# re-bent_hum_singe.net
KiCad netlist of a schematic drawn in EAGLE
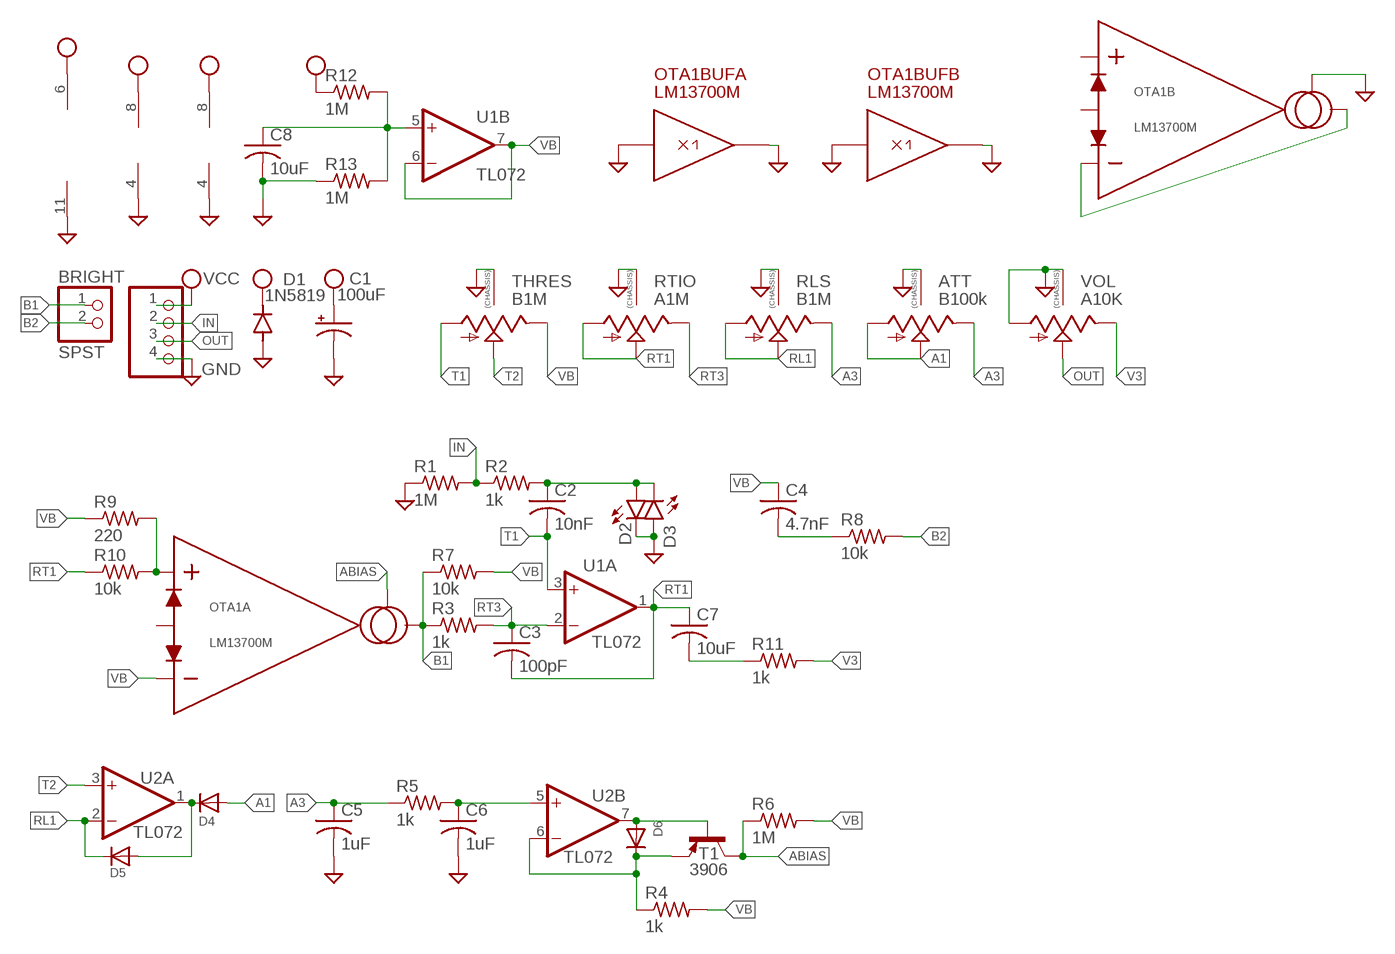
[diagram p0: schematic, sheet 1]

(export (version "E")
  (design (tool "Eeschema 10.0.6"))
  (components
    (comp (ref "ATT")
      (value "B100k")
      (footprint "eagle-import:9MM_SNAP-IN_POT")
      (libsource (lib "eagle-import") (part "9MM_SNAP-IN_POT_CHASSIS"))
    )
    (comp (ref "BRIGHT")
      (value "SPST")
      (footprint "eagle-import:1X02")
      (libsource (lib "eagle-import") (part "PINHD-1X2"))
    )
    (comp (ref "C1")
      (value "100uF")
      (footprint "eagle-import:PAN_B_SMD+THRU")
      (libsource (lib "eagle-import") (part "CAP_SMD+THRUPAN_B"))
    )
    (comp (ref "C2")
      (value "10nF")
      (footprint "eagle-import:C0603")
      (libsource (lib "eagle-import") (part "adafruit_420_C-USC0603"))
    )
    (comp (ref "C3")
      (value "100pF")
      (footprint "eagle-import:C0603")
      (libsource (lib "eagle-import") (part "adafruit_420_C-USC0603"))
    )
    (comp (ref "C4")
      (value "4.7nF")
      (footprint "eagle-import:C0603")
      (libsource (lib "eagle-import") (part "adafruit_420_C-USC0603"))
    )
    (comp (ref "C5")
      (value "1uF")
      (footprint "eagle-import:C0805")
      (libsource (lib "eagle-import") (part "C-USC0805"))
    )
    (comp (ref "C6")
      (value "1uF")
      (footprint "eagle-import:C0805")
      (libsource (lib "eagle-import") (part "C-USC0805"))
    )
    (comp (ref "C7")
      (value "10uF")
      (footprint "eagle-import:C1206")
      (libsource (lib "eagle-import") (part "C-USC1206"))
    )
    (comp (ref "C8")
      (value "10uF")
      (footprint "eagle-import:C1206")
      (libsource (lib "eagle-import") (part "C-USC1206"))
    )
    (comp (ref "D1")
      (value "1N5819")
      (footprint "eagle-import:SOD123")
      (libsource (lib "eagle-import") (part "DIODE-SOD123"))
    )
    (comp (ref "D2")
      (value "LED0603")
      (footprint "eagle-import:LED-0603")
      (libsource (lib "eagle-import") (part "LED0603"))
    )
    (comp (ref "D3")
      (value "LED0603")
      (footprint "eagle-import:LED-0603")
      (libsource (lib "eagle-import") (part "LED0603"))
    )
    (comp (ref "D4")
      (value "DIODESOD-123")
      (footprint "eagle-import:SOD-123")
      (libsource (lib "eagle-import") (part "DIODESOD-123"))
    )
    (comp (ref "D5")
      (value "DIODESOD-123")
      (footprint "eagle-import:SOD-123")
      (libsource (lib "eagle-import") (part "DIODESOD-123"))
    )
    (comp (ref "D6")
      (value "DIODESOD-123")
      (footprint "eagle-import:SOD-123")
      (libsource (lib "eagle-import") (part "DIODESOD-123"))
    )
    (comp (ref "JP1")
      (value "PINHD-1X4")
      (footprint "eagle-import:1X04")
      (libsource (lib "eagle-import") (part "PINHD-1X4"))
    )
    (comp (ref "OTA1")
      (value "LM13700M")
      (footprint "eagle-import:SO16")
      (libsource (lib "eagle-import") (part "LM13700M"))
    )
    (comp (ref "R1")
      (value "1M")
      (footprint "eagle-import:R0603")
      (libsource (lib "eagle-import") (part "R-US_R0603"))
    )
    (comp (ref "R2")
      (value "1k")
      (footprint "eagle-import:R0603")
      (libsource (lib "eagle-import") (part "R-US_R0603"))
    )
    (comp (ref "R3")
      (value "1k")
      (footprint "eagle-import:R0603")
      (libsource (lib "eagle-import") (part "R-US_R0603"))
    )
    (comp (ref "R4")
      (value "1k")
      (footprint "eagle-import:R0603")
      (libsource (lib "eagle-import") (part "R-US_R0603"))
    )
    (comp (ref "R5")
      (value "1k")
      (footprint "eagle-import:R0603")
      (libsource (lib "eagle-import") (part "R-US_R0603"))
    )
    (comp (ref "R6")
      (value "1M")
      (footprint "eagle-import:R0603")
      (libsource (lib "eagle-import") (part "R-US_R0603"))
    )
    (comp (ref "R7")
      (value "10k")
      (footprint "eagle-import:R0603")
      (libsource (lib "eagle-import") (part "R-US_R0603"))
    )
    (comp (ref "R8")
      (value "10k")
      (footprint "eagle-import:R0603")
      (libsource (lib "eagle-import") (part "R-US_R0603"))
    )
    (comp (ref "R9")
      (value "220")
      (footprint "eagle-import:R0603")
      (libsource (lib "eagle-import") (part "R-US_R0603"))
    )
    (comp (ref "R10")
      (value "10k")
      (footprint "eagle-import:R0603")
      (libsource (lib "eagle-import") (part "R-US_R0603"))
    )
    (comp (ref "R11")
      (value "1k")
      (footprint "eagle-import:R0603")
      (libsource (lib "eagle-import") (part "R-US_R0603"))
    )
    (comp (ref "R12")
      (value "1M")
      (footprint "eagle-import:R0603")
      (libsource (lib "eagle-import") (part "R-US_R0603"))
    )
    (comp (ref "R13")
      (value "1M")
      (footprint "eagle-import:R0603")
      (libsource (lib "eagle-import") (part "R-US_R0603"))
    )
    (comp (ref "RLS")
      (value "B1M")
      (footprint "eagle-import:9MM_SNAP-IN_POT")
      (libsource (lib "eagle-import") (part "9MM_SNAP-IN_POT_CHASSIS"))
    )
    (comp (ref "RTIO")
      (value "A1M")
      (footprint "eagle-import:9MM_SNAP-IN_POT")
      (libsource (lib "eagle-import") (part "9MM_SNAP-IN_POT_CHASSIS"))
    )
    (comp (ref "T1")
      (value "3906")
      (footprint "eagle-import:SOT23-BEC")
      (libsource (lib "eagle-import") (part "-PNP-SOT23-BECMMBT3906LT1"))
    )
    (comp (ref "THRES")
      (value "B1M")
      (footprint "eagle-import:9MM_SNAP-IN_POT")
      (libsource (lib "eagle-import") (part "9MM_SNAP-IN_POT_CHASSIS"))
    )
    (comp (ref "U1")
      (value "TL072")
      (footprint "eagle-import:TSSOP-8")
      (libsource (lib "eagle-import") (part "TL072TSSOP"))
    )
    (comp (ref "U2")
      (value "TL072")
      (footprint "eagle-import:TSSOP-8")
      (libsource (lib "eagle-import") (part "TL072TSSOP"))
    )
    (comp (ref "VOL")
      (value "A10K")
      (footprint "eagle-import:9MM_SNAP-IN_POT")
      (libsource (lib "eagle-import") (part "9MM_SNAP-IN_POT_CHASSIS"))
    )
  )
  (nets
    (net (code "1") (name "A1") (class "Default")
      (node (ref "ATT") (pin "1") (pinfunction "A_1") (pintype "passive"))
      (node (ref "ATT") (pin "2") (pinfunction "S_2") (pintype "passive"))
      (node (ref "D4") (pin "A") (pinfunction "A_A") (pintype "passive"))
    )
    (net (code "2") (name "A3") (class "Default")
      (node (ref "ATT") (pin "3") (pinfunction "E_3") (pintype "passive"))
      (node (ref "C5") (pin "1") (pinfunction "1_1") (pintype "passive"))
      (node (ref "R5") (pin "1") (pinfunction "1_1") (pintype "passive"))
      (node (ref "RLS") (pin "3") (pinfunction "E_3") (pintype "passive"))
    )
    (net (code "3") (name "ABIAS") (class "Default")
      (node (ref "OTA1") (pin "1") (pinfunction "IABC_1") (pintype "input"))
      (node (ref "R6") (pin "1") (pinfunction "1_1") (pintype "passive"))
      (node (ref "T1") (pin "C") (pinfunction "C_C") (pintype "passive"))
    )
    (net (code "4") (name "B1") (class "Default")
      (node (ref "BRIGHT") (pin "1") (pinfunction "1_1") (pintype "passive"))
      (node (ref "OTA1") (pin "5") (pinfunction "IOUT_5") (pintype "output"))
      (node (ref "R3") (pin "1") (pinfunction "1_1") (pintype "passive"))
      (node (ref "R7") (pin "1") (pinfunction "1_1") (pintype "passive"))
    )
    (net (code "5") (name "B2") (class "Default")
      (node (ref "BRIGHT") (pin "2") (pinfunction "2_2") (pintype "passive"))
      (node (ref "R8") (pin "2") (pinfunction "2_2") (pintype "passive"))
    )
    (net (code "6") (name "GND") (class "Default")
      (node (ref "ATT") (pin "CHASSIS1") (pinfunction "P$1_CHASSIS1") (pintype "passive"))
      (node (ref "ATT") (pin "CHASSIS2") (pinfunction "P$1_CHASSIS2") (pintype "passive"))
      (node (ref "C1") (pin "-") (pinfunction "-_-") (pintype "passive"))
      (node (ref "C1") (pin "--") (pinfunction "-_--") (pintype "passive"))
      (node (ref "C5") (pin "2") (pinfunction "2_2") (pintype "passive"))
      (node (ref "C6") (pin "2") (pinfunction "2_2") (pintype "passive"))
      (node (ref "C8") (pin "2") (pinfunction "2_2") (pintype "passive"))
      (node (ref "D1") (pin "A") (pinfunction "A_A") (pintype "passive"))
      (node (ref "D2") (pin "C") (pinfunction "C_C") (pintype "passive"))
      (node (ref "D3") (pin "A") (pinfunction "A_A") (pintype "passive"))
      (node (ref "JP1") (pin "4") (pinfunction "4_4") (pintype "passive"))
      (node (ref "OTA1") (pin "11") (pinfunction "VEE_11") (pintype "power_in"))
      (node (ref "OTA1") (pin "16") (pinfunction "IABC_16") (pintype "input"))
      (node (ref "OTA1") (pin "8") (pinfunction "OUT_8") (pintype "bidirectional"))
      (node (ref "OTA1") (pin "9") (pinfunction "OUT_9") (pintype "bidirectional"))
      (node (ref "R1") (pin "1") (pinfunction "1_1") (pintype "passive"))
      (node (ref "R13") (pin "1") (pinfunction "1_1") (pintype "passive"))
      (node (ref "RLS") (pin "CHASSIS1") (pinfunction "P$1_CHASSIS1") (pintype "passive"))
      (node (ref "RLS") (pin "CHASSIS2") (pinfunction "P$1_CHASSIS2") (pintype "passive"))
      (node (ref "RTIO") (pin "CHASSIS1") (pinfunction "P$1_CHASSIS1") (pintype "passive"))
      (node (ref "RTIO") (pin "CHASSIS2") (pinfunction "P$1_CHASSIS2") (pintype "passive"))
      (node (ref "THRES") (pin "CHASSIS1") (pinfunction "P$1_CHASSIS1") (pintype "passive"))
      (node (ref "THRES") (pin "CHASSIS2") (pinfunction "P$1_CHASSIS2") (pintype "passive"))
      (node (ref "U1") (pin "4") (pinfunction "V-_4") (pintype "power_in"))
      (node (ref "U2") (pin "4") (pinfunction "V-_4") (pintype "power_in"))
      (node (ref "VOL") (pin "1") (pinfunction "A_1") (pintype "passive"))
      (node (ref "VOL") (pin "CHASSIS1") (pinfunction "P$1_CHASSIS1") (pintype "passive"))
      (node (ref "VOL") (pin "CHASSIS2") (pinfunction "P$1_CHASSIS2") (pintype "passive"))
    )
    (net (code "7") (name "IN") (class "Default")
      (node (ref "JP1") (pin "2") (pinfunction "2_2") (pintype "passive"))
      (node (ref "R1") (pin "2") (pinfunction "2_2") (pintype "passive"))
      (node (ref "R2") (pin "1") (pinfunction "1_1") (pintype "passive"))
    )
    (net (code "8") (name "Net-(C2-Pad1)") (class "Default")
      (node (ref "C2") (pin "1") (pinfunction "1_1") (pintype "passive"))
      (node (ref "D2") (pin "A") (pinfunction "A_A") (pintype "passive"))
      (node (ref "D3") (pin "C") (pinfunction "C_C") (pintype "passive"))
      (node (ref "R2") (pin "2") (pinfunction "2_2") (pintype "passive"))
    )
    (net (code "9") (name "Net-(C4-Pad2)") (class "Default")
      (node (ref "C4") (pin "2") (pinfunction "2_2") (pintype "passive"))
      (node (ref "R8") (pin "1") (pinfunction "1_1") (pintype "passive"))
    )
    (net (code "10") (name "Net-(C7-Pad2)") (class "Default")
      (node (ref "C7") (pin "2") (pinfunction "2_2") (pintype "passive"))
      (node (ref "R11") (pin "1") (pinfunction "1_1") (pintype "passive"))
    )
    (net (code "11") (name "Net-(OTA1A-IN+)") (class "Default")
      (node (ref "OTA1") (pin "3") (pinfunction "IN+_3") (pintype "input"))
      (node (ref "R10") (pin "2") (pinfunction "2_2") (pintype "passive"))
      (node (ref "R9") (pin "2") (pinfunction "2_2") (pintype "passive"))
    )
    (net (code "12") (name "Net-(OTA1B-IN-)") (class "Default")
      (node (ref "OTA1") (pin "12") (pinfunction "IOUT_12") (pintype "output"))
      (node (ref "OTA1") (pin "13") (pinfunction "IN-_13") (pintype "input"))
    )
    (net (code "13") (name "Net-(U1B-+IN)") (class "Default")
      (node (ref "C8") (pin "1") (pinfunction "1_1") (pintype "passive"))
      (node (ref "R12") (pin "2") (pinfunction "2_2") (pintype "passive"))
      (node (ref "R13") (pin "2") (pinfunction "2_2") (pintype "passive"))
      (node (ref "U1") (pin "5") (pinfunction "+IN_5") (pintype "input"))
    )
    (net (code "14") (name "Net-(U2A-OUT)") (class "Default")
      (node (ref "D4") (pin "C") (pinfunction "C_C") (pintype "passive"))
      (node (ref "D5") (pin "A") (pinfunction "A_A") (pintype "passive"))
      (node (ref "U2") (pin "1") (pinfunction "OUT_1") (pintype "output"))
    )
    (net (code "15") (name "Net-(U2B-+IN)") (class "Default")
      (node (ref "C6") (pin "1") (pinfunction "1_1") (pintype "passive"))
      (node (ref "R5") (pin "2") (pinfunction "2_2") (pintype "passive"))
      (node (ref "U2") (pin "5") (pinfunction "+IN_5") (pintype "input"))
    )
    (net (code "16") (name "Net-(U2B--IN)") (class "Default")
      (node (ref "D6") (pin "C") (pinfunction "C_C") (pintype "passive"))
      (node (ref "R4") (pin "1") (pinfunction "1_1") (pintype "passive"))
      (node (ref "T1") (pin "E") (pinfunction "E_E") (pintype "passive"))
      (node (ref "U2") (pin "6") (pinfunction "-IN_6") (pintype "input"))
    )
    (net (code "17") (name "Net-(U2B-OUT)") (class "Default")
      (node (ref "D6") (pin "A") (pinfunction "A_A") (pintype "passive"))
      (node (ref "T1") (pin "B") (pinfunction "B_B") (pintype "passive"))
      (node (ref "U2") (pin "7") (pinfunction "OUT_7") (pintype "output"))
    )
    (net (code "18") (name "OUT") (class "Default")
      (node (ref "JP1") (pin "3") (pinfunction "3_3") (pintype "passive"))
      (node (ref "VOL") (pin "2") (pinfunction "S_2") (pintype "passive"))
    )
    (net (code "19") (name "RL1") (class "Default")
      (node (ref "D5") (pin "C") (pinfunction "C_C") (pintype "passive"))
      (node (ref "RLS") (pin "1") (pinfunction "A_1") (pintype "passive"))
      (node (ref "RLS") (pin "2") (pinfunction "S_2") (pintype "passive"))
      (node (ref "U2") (pin "2") (pinfunction "-IN_2") (pintype "input"))
    )
    (net (code "20") (name "RT1") (class "Default")
      (node (ref "C3") (pin "2") (pinfunction "2_2") (pintype "passive"))
      (node (ref "C7") (pin "1") (pinfunction "1_1") (pintype "passive"))
      (node (ref "R10") (pin "1") (pinfunction "1_1") (pintype "passive"))
      (node (ref "RTIO") (pin "1") (pinfunction "A_1") (pintype "passive"))
      (node (ref "RTIO") (pin "2") (pinfunction "S_2") (pintype "passive"))
      (node (ref "U1") (pin "1") (pinfunction "OUT_1") (pintype "output"))
    )
    (net (code "21") (name "RT3") (class "Default")
      (node (ref "C3") (pin "1") (pinfunction "1_1") (pintype "passive"))
      (node (ref "R3") (pin "2") (pinfunction "2_2") (pintype "passive"))
      (node (ref "RTIO") (pin "3") (pinfunction "E_3") (pintype "passive"))
      (node (ref "U1") (pin "2") (pinfunction "-IN_2") (pintype "input"))
    )
    (net (code "22") (name "T1") (class "Default")
      (node (ref "C2") (pin "2") (pinfunction "2_2") (pintype "passive"))
      (node (ref "THRES") (pin "1") (pinfunction "A_1") (pintype "passive"))
      (node (ref "U1") (pin "3") (pinfunction "+IN_3") (pintype "input"))
    )
    (net (code "23") (name "T2") (class "Default")
      (node (ref "THRES") (pin "2") (pinfunction "S_2") (pintype "passive"))
      (node (ref "U2") (pin "3") (pinfunction "+IN_3") (pintype "input"))
    )
    (net (code "24") (name "V3") (class "Default")
      (node (ref "R11") (pin "2") (pinfunction "2_2") (pintype "passive"))
      (node (ref "VOL") (pin "3") (pinfunction "E_3") (pintype "passive"))
    )
    (net (code "25") (name "VB") (class "Default")
      (node (ref "C4") (pin "1") (pinfunction "1_1") (pintype "passive"))
      (node (ref "OTA1") (pin "4") (pinfunction "IN-_4") (pintype "input"))
      (node (ref "R4") (pin "2") (pinfunction "2_2") (pintype "passive"))
      (node (ref "R6") (pin "2") (pinfunction "2_2") (pintype "passive"))
      (node (ref "R7") (pin "2") (pinfunction "2_2") (pintype "passive"))
      (node (ref "R9") (pin "1") (pinfunction "1_1") (pintype "passive"))
      (node (ref "THRES") (pin "3") (pinfunction "E_3") (pintype "passive"))
      (node (ref "U1") (pin "6") (pinfunction "-IN_6") (pintype "input"))
      (node (ref "U1") (pin "7") (pinfunction "OUT_7") (pintype "output"))
    )
    (net (code "26") (name "VCC") (class "Default")
      (node (ref "C1") (pin "+") (pinfunction "+_+") (pintype "passive"))
      (node (ref "C1") (pin "++") (pinfunction "+_++") (pintype "passive"))
      (node (ref "D1") (pin "C") (pinfunction "C_C") (pintype "passive"))
      (node (ref "JP1") (pin "1") (pinfunction "1_1") (pintype "passive"))
      (node (ref "OTA1") (pin "6") (pinfunction "VCC_6") (pintype "power_in"))
      (node (ref "R12") (pin "1") (pinfunction "1_1") (pintype "passive"))
      (node (ref "U1") (pin "8") (pinfunction "V+_8") (pintype "power_in"))
      (node (ref "U2") (pin "8") (pinfunction "V+_8") (pintype "power_in"))
    )
    (net (code "27") (name "unconnected-(OTA1A-BIAS-Pad2)") (class "Default")
      (node (ref "OTA1") (pin "2") (pinfunction "BIAS_2") (pintype "input"))
    )
    (net (code "28") (name "unconnected-(OTA1B-BIAS-Pad15)") (class "Default")
      (node (ref "OTA1") (pin "15") (pinfunction "BIAS_15") (pintype "input"))
    )
    (net (code "29") (name "unconnected-(OTA1B-IN+-Pad14)") (class "Default")
      (node (ref "OTA1") (pin "14") (pinfunction "IN+_14") (pintype "input"))
    )
    (net (code "30") (name "unconnected-(OTA1C-IN-Pad7)") (class "Default")
      (node (ref "OTA1") (pin "7") (pinfunction "IN_7") (pintype "bidirectional"))
    )
    (net (code "31") (name "unconnected-(OTA1D-IN-Pad10)") (class "Default")
      (node (ref "OTA1") (pin "10") (pinfunction "IN_10") (pintype "bidirectional"))
    )
  )
)
